# motor_board.net
KiCad netlist of a schematic drawn in EAGLE
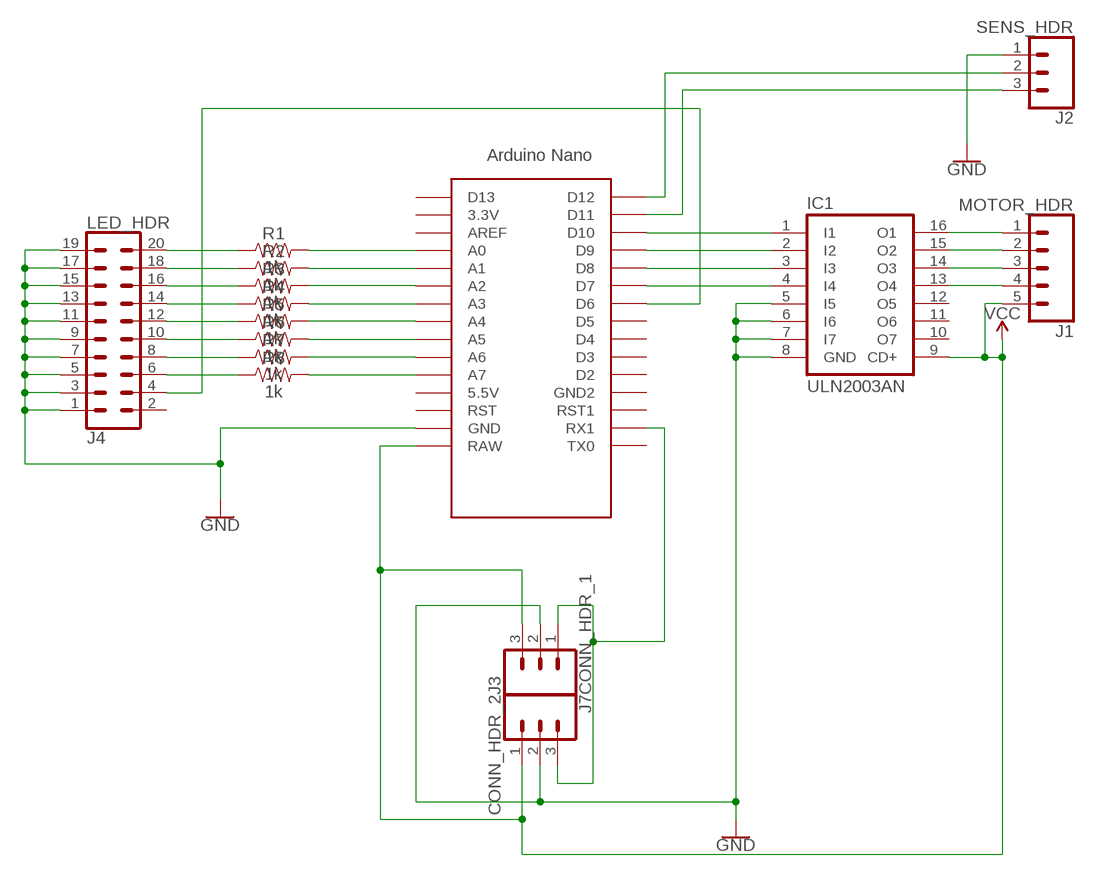
[diagram p0: schematic, sheet 1]

(export (version "E")
  (design (tool "Eeschema 10.0.6"))
  (components
    (comp (ref "IC1")
      (value "ULN2003AN")
      (footprint "eagle-import:DIL16")
      (libsource (lib "eagle-import") (part "ULN2003AN"))
    )
    (comp (ref "J1")
      (value "MOTOR_HDR")
      (footprint "eagle-import:1X05")
      (libsource (lib "eagle-import") (part "CONN_05"))
    )
    (comp (ref "J2")
      (value "SENS_HDR")
      (footprint "eagle-import:1X03")
      (libsource (lib "eagle-import") (part "CONN_03"))
    )
    (comp (ref "J3")
      (value "CONN_HDR_1")
      (footprint "eagle-import:1X03")
      (libsource (lib "eagle-import") (part "CONN_03"))
    )
    (comp (ref "J4")
      (value "LED_HDR")
      (footprint "eagle-import:2X10")
      (libsource (lib "eagle-import") (part "CONN_10X2"))
    )
    (comp (ref "J7")
      (value "CONN_HDR_2")
      (footprint "eagle-import:1X03")
      (libsource (lib "eagle-import") (part "CONN_03"))
    )
    (comp (ref "R1")
      (value "1k")
      (footprint "eagle-import:AXIAL-0.3")
      (libsource (lib "eagle-import") (part "1KOHM-HORIZ-1/4W-1%"))
    )
    (comp (ref "R2")
      (value "1k")
      (footprint "eagle-import:AXIAL-0.3")
      (libsource (lib "eagle-import") (part "1KOHM-HORIZ-1/4W-1%"))
    )
    (comp (ref "R3")
      (value "1k")
      (footprint "eagle-import:AXIAL-0.3")
      (libsource (lib "eagle-import") (part "1KOHM-HORIZ-1/4W-1%"))
    )
    (comp (ref "R4")
      (value "1k")
      (footprint "eagle-import:AXIAL-0.3")
      (libsource (lib "eagle-import") (part "1KOHM-HORIZ-1/4W-1%"))
    )
    (comp (ref "R5")
      (value "1k")
      (footprint "eagle-import:AXIAL-0.3")
      (libsource (lib "eagle-import") (part "1KOHM-HORIZ-1/4W-1%"))
    )
    (comp (ref "R6")
      (value "1k")
      (footprint "eagle-import:AXIAL-0.3")
      (libsource (lib "eagle-import") (part "1KOHM-HORIZ-1/4W-1%"))
    )
    (comp (ref "R7")
      (value "1k")
      (footprint "eagle-import:AXIAL-0.3")
      (libsource (lib "eagle-import") (part "1KOHM-HORIZ-1/4W-1%"))
    )
    (comp (ref "R8")
      (value "1k")
      (footprint "eagle-import:AXIAL-0.3")
      (libsource (lib "eagle-import") (part "1KOHM-HORIZ-1/4W-1%"))
    )
    (comp (ref "U$1")
      (value "NANO")
      (footprint "eagle-import:NANO")
      (libsource (lib "eagle-import") (part "NANO"))
    )
  )
  (nets
    (net (code "1") (name "GND") (class "Default")
      (node (ref "IC1") (pin "5") (pinfunction "I5_5") (pintype "input"))
      (node (ref "IC1") (pin "6") (pinfunction "I6_6") (pintype "input"))
      (node (ref "IC1") (pin "7") (pinfunction "I7_7") (pintype "input"))
      (node (ref "IC1") (pin "8") (pinfunction "GND_8") (pintype "power_in"))
      (node (ref "J2") (pin "1") (pinfunction "1_1") (pintype "passive"))
      (node (ref "J3") (pin "2") (pinfunction "2_2") (pintype "passive"))
      (node (ref "J4") (pin "1") (pinfunction "1_1") (pintype "passive"))
      (node (ref "J4") (pin "11") (pinfunction "11_11") (pintype "passive"))
      (node (ref "J4") (pin "13") (pinfunction "13_13") (pintype "passive"))
      (node (ref "J4") (pin "15") (pinfunction "15_15") (pintype "passive"))
      (node (ref "J4") (pin "17") (pinfunction "17_17") (pintype "passive"))
      (node (ref "J4") (pin "19") (pinfunction "19_19") (pintype "passive"))
      (node (ref "J4") (pin "3") (pinfunction "3_3") (pintype "passive"))
      (node (ref "J4") (pin "5") (pinfunction "5_5") (pintype "passive"))
      (node (ref "J4") (pin "7") (pinfunction "7_7") (pintype "passive"))
      (node (ref "J4") (pin "9") (pinfunction "9_9") (pintype "passive"))
      (node (ref "J7") (pin "2") (pinfunction "2_2") (pintype "passive"))
      (node (ref "U$1") (pin "GND") (pinfunction "GND_GND") (pintype "bidirectional"))
    )
    (net (code "2") (name "Net-(IC1-I1)") (class "Default")
      (node (ref "IC1") (pin "1") (pinfunction "I1_1") (pintype "input"))
      (node (ref "U$1") (pin "D10") (pinfunction "D10_D10") (pintype "bidirectional"))
    )
    (net (code "3") (name "Net-(IC1-I2)") (class "Default")
      (node (ref "IC1") (pin "2") (pinfunction "I2_2") (pintype "input"))
      (node (ref "U$1") (pin "D9") (pinfunction "D9_D9") (pintype "bidirectional"))
    )
    (net (code "4") (name "Net-(IC1-I3)") (class "Default")
      (node (ref "IC1") (pin "3") (pinfunction "I3_3") (pintype "input"))
      (node (ref "U$1") (pin "D8") (pinfunction "D8_D8") (pintype "bidirectional"))
    )
    (net (code "5") (name "Net-(IC1-I4)") (class "Default")
      (node (ref "IC1") (pin "4") (pinfunction "I4_4") (pintype "input"))
      (node (ref "U$1") (pin "D7") (pinfunction "D7_D7") (pintype "bidirectional"))
    )
    (net (code "6") (name "Net-(IC1-O1)") (class "Default")
      (node (ref "IC1") (pin "16") (pinfunction "O1_16") (pintype "open_collector"))
      (node (ref "J1") (pin "1") (pinfunction "1_1") (pintype "passive"))
    )
    (net (code "7") (name "Net-(IC1-O2)") (class "Default")
      (node (ref "IC1") (pin "15") (pinfunction "O2_15") (pintype "open_collector"))
      (node (ref "J1") (pin "2") (pinfunction "2_2") (pintype "passive"))
    )
    (net (code "8") (name "Net-(IC1-O3)") (class "Default")
      (node (ref "IC1") (pin "14") (pinfunction "O3_14") (pintype "open_collector"))
      (node (ref "J1") (pin "3") (pinfunction "3_3") (pintype "passive"))
    )
    (net (code "9") (name "Net-(IC1-O4)") (class "Default")
      (node (ref "IC1") (pin "13") (pinfunction "O4_13") (pintype "open_collector"))
      (node (ref "J1") (pin "4") (pinfunction "4_4") (pintype "passive"))
    )
    (net (code "10") (name "Net-(J2-Pad2)") (class "Default")
      (node (ref "J2") (pin "2") (pinfunction "2_2") (pintype "passive"))
      (node (ref "U$1") (pin "D12") (pinfunction "D12_D12") (pintype "bidirectional"))
    )
    (net (code "11") (name "Net-(J2-Pad3)") (class "Default")
      (node (ref "J2") (pin "3") (pinfunction "3_3") (pintype "passive"))
      (node (ref "U$1") (pin "D11") (pinfunction "D11_D11") (pintype "bidirectional"))
    )
    (net (code "12") (name "Net-(J3-Pad1)") (class "Default")
      (node (ref "J3") (pin "1") (pinfunction "1_1") (pintype "passive"))
      (node (ref "J7") (pin "3") (pinfunction "3_3") (pintype "passive"))
      (node (ref "U$1") (pin "RX1") (pinfunction "RX1_RX1") (pintype "bidirectional"))
    )
    (net (code "13") (name "Net-(J4-Pad4)") (class "Default")
      (node (ref "J4") (pin "4") (pinfunction "4_4") (pintype "passive"))
      (node (ref "U$1") (pin "D6") (pinfunction "D6_D6") (pintype "bidirectional"))
    )
    (net (code "14") (name "Net-(R1-1)") (class "Default")
      (node (ref "J4") (pin "20") (pinfunction "20_20") (pintype "passive"))
      (node (ref "R1") (pin "P$1") (pinfunction "1_P$1") (pintype "passive"))
    )
    (net (code "15") (name "Net-(R1-2)") (class "Default")
      (node (ref "R1") (pin "P$2") (pinfunction "2_P$2") (pintype "passive"))
      (node (ref "U$1") (pin "A0") (pinfunction "A0_A0") (pintype "bidirectional"))
    )
    (net (code "16") (name "Net-(R2-1)") (class "Default")
      (node (ref "J4") (pin "18") (pinfunction "18_18") (pintype "passive"))
      (node (ref "R2") (pin "P$1") (pinfunction "1_P$1") (pintype "passive"))
    )
    (net (code "17") (name "Net-(R2-2)") (class "Default")
      (node (ref "R2") (pin "P$2") (pinfunction "2_P$2") (pintype "passive"))
      (node (ref "U$1") (pin "A1") (pinfunction "A1_A1") (pintype "bidirectional"))
    )
    (net (code "18") (name "Net-(R3-1)") (class "Default")
      (node (ref "J4") (pin "16") (pinfunction "16_16") (pintype "passive"))
      (node (ref "R3") (pin "P$1") (pinfunction "1_P$1") (pintype "passive"))
    )
    (net (code "19") (name "Net-(R3-2)") (class "Default")
      (node (ref "R3") (pin "P$2") (pinfunction "2_P$2") (pintype "passive"))
      (node (ref "U$1") (pin "A2") (pinfunction "A2_A2") (pintype "bidirectional"))
    )
    (net (code "20") (name "Net-(R4-1)") (class "Default")
      (node (ref "J4") (pin "14") (pinfunction "14_14") (pintype "passive"))
      (node (ref "R4") (pin "P$1") (pinfunction "1_P$1") (pintype "passive"))
    )
    (net (code "21") (name "Net-(R4-2)") (class "Default")
      (node (ref "R4") (pin "P$2") (pinfunction "2_P$2") (pintype "passive"))
      (node (ref "U$1") (pin "A3") (pinfunction "A3_A3") (pintype "bidirectional"))
    )
    (net (code "22") (name "Net-(R5-1)") (class "Default")
      (node (ref "J4") (pin "12") (pinfunction "12_12") (pintype "passive"))
      (node (ref "R5") (pin "P$1") (pinfunction "1_P$1") (pintype "passive"))
    )
    (net (code "23") (name "Net-(R5-2)") (class "Default")
      (node (ref "R5") (pin "P$2") (pinfunction "2_P$2") (pintype "passive"))
      (node (ref "U$1") (pin "A4") (pinfunction "A4_A4") (pintype "bidirectional"))
    )
    (net (code "24") (name "Net-(R6-1)") (class "Default")
      (node (ref "J4") (pin "10") (pinfunction "10_10") (pintype "passive"))
      (node (ref "R6") (pin "P$1") (pinfunction "1_P$1") (pintype "passive"))
    )
    (net (code "25") (name "Net-(R6-2)") (class "Default")
      (node (ref "R6") (pin "P$2") (pinfunction "2_P$2") (pintype "passive"))
      (node (ref "U$1") (pin "A5") (pinfunction "A5_A5") (pintype "bidirectional"))
    )
    (net (code "26") (name "Net-(R7-1)") (class "Default")
      (node (ref "J4") (pin "8") (pinfunction "8_8") (pintype "passive"))
      (node (ref "R7") (pin "P$1") (pinfunction "1_P$1") (pintype "passive"))
    )
    (net (code "27") (name "Net-(R7-2)") (class "Default")
      (node (ref "R7") (pin "P$2") (pinfunction "2_P$2") (pintype "passive"))
      (node (ref "U$1") (pin "A6") (pinfunction "A6_A6") (pintype "bidirectional"))
    )
    (net (code "28") (name "Net-(R8-1)") (class "Default")
      (node (ref "J4") (pin "6") (pinfunction "6_6") (pintype "passive"))
      (node (ref "R8") (pin "P$1") (pinfunction "1_P$1") (pintype "passive"))
    )
    (net (code "29") (name "Net-(R8-2)") (class "Default")
      (node (ref "R8") (pin "P$2") (pinfunction "2_P$2") (pintype "passive"))
      (node (ref "U$1") (pin "A7") (pinfunction "A7_A7") (pintype "bidirectional"))
    )
    (net (code "30") (name "VCC") (class "Default")
      (node (ref "IC1") (pin "9") (pinfunction "CD+_9") (pintype "passive"))
      (node (ref "J1") (pin "5") (pinfunction "5_5") (pintype "passive"))
      (node (ref "J3") (pin "3") (pinfunction "3_3") (pintype "passive"))
      (node (ref "J7") (pin "1") (pinfunction "1_1") (pintype "passive"))
      (node (ref "U$1") (pin "RAW") (pinfunction "RAW_RAW") (pintype "bidirectional"))
    )
    (net (code "31") (name "unconnected-(IC1-O5-Pad12)") (class "Default")
      (node (ref "IC1") (pin "12") (pinfunction "O5_12") (pintype "open_collector"))
    )
    (net (code "32") (name "unconnected-(IC1-O6-Pad11)") (class "Default")
      (node (ref "IC1") (pin "11") (pinfunction "O6_11") (pintype "open_collector"))
    )
    (net (code "33") (name "unconnected-(IC1-O7-Pad10)") (class "Default")
      (node (ref "IC1") (pin "10") (pinfunction "O7_10") (pintype "open_collector"))
    )
    (net (code "34") (name "unconnected-(J4-Pad2)") (class "Default")
      (node (ref "J4") (pin "2") (pinfunction "2_2") (pintype "passive"))
    )
    (net (code "35") (name "unconnected-(U$1-5.5V-Pad5V)") (class "Default")
      (node (ref "U$1") (pin "5V") (pinfunction "5.5V_5V") (pintype "bidirectional"))
    )
    (net (code "36") (name "unconnected-(U$1-GND2-PadGND1)") (class "Default")
      (node (ref "U$1") (pin "GND1") (pinfunction "GND2_GND1") (pintype "bidirectional"))
    )
    (net (code "37") (name "unconnected-(U$1-Pad3.3V)") (class "Default")
      (node (ref "U$1") (pin "3.3V") (pinfunction "3.3V_3.3V") (pintype "bidirectional"))
    )
    (net (code "38") (name "unconnected-(U$1-PadAREF)") (class "Default")
      (node (ref "U$1") (pin "AREF") (pinfunction "AREF_AREF") (pintype "bidirectional"))
    )
    (net (code "39") (name "unconnected-(U$1-PadD2)") (class "Default")
      (node (ref "U$1") (pin "D2") (pinfunction "D2_D2") (pintype "bidirectional"))
    )
    (net (code "40") (name "unconnected-(U$1-PadD3)") (class "Default")
      (node (ref "U$1") (pin "D3") (pinfunction "D3_D3") (pintype "bidirectional"))
    )
    (net (code "41") (name "unconnected-(U$1-PadD4)") (class "Default")
      (node (ref "U$1") (pin "D4") (pinfunction "D4_D4") (pintype "bidirectional"))
    )
    (net (code "42") (name "unconnected-(U$1-PadD5)") (class "Default")
      (node (ref "U$1") (pin "D5") (pinfunction "D5_D5") (pintype "bidirectional"))
    )
    (net (code "43") (name "unconnected-(U$1-PadD13)") (class "Default")
      (node (ref "U$1") (pin "D13") (pinfunction "D13_D13") (pintype "bidirectional"))
    )
    (net (code "44") (name "unconnected-(U$1-PadICSP1)") (class "Default")
      (node (ref "U$1") (pin "ICSP1") (pinfunction "ICSP1_ICSP1") (pintype "bidirectional"))
    )
    (net (code "45") (name "unconnected-(U$1-PadICSP2)") (class "Default")
      (node (ref "U$1") (pin "ICSP2") (pinfunction "ICSP2_ICSP2") (pintype "bidirectional"))
    )
    (net (code "46") (name "unconnected-(U$1-PadICSP3)") (class "Default")
      (node (ref "U$1") (pin "ICSP3") (pinfunction "ICSP3_ICSP3") (pintype "bidirectional"))
    )
    (net (code "47") (name "unconnected-(U$1-PadICSP4)") (class "Default")
      (node (ref "U$1") (pin "ICSP4") (pinfunction "ICSP4_ICSP4") (pintype "bidirectional"))
    )
    (net (code "48") (name "unconnected-(U$1-PadICSP5)") (class "Default")
      (node (ref "U$1") (pin "ICSP5") (pinfunction "ICSP5_ICSP5") (pintype "bidirectional"))
    )
    (net (code "49") (name "unconnected-(U$1-PadICSP6)") (class "Default")
      (node (ref "U$1") (pin "ICSP6") (pinfunction "ICSP6_ICSP6") (pintype "bidirectional"))
    )
    (net (code "50") (name "unconnected-(U$1-PadRST)") (class "Default")
      (node (ref "U$1") (pin "RST") (pinfunction "RST_RST") (pintype "bidirectional"))
    )
    (net (code "51") (name "unconnected-(U$1-PadRST1)") (class "Default")
      (node (ref "U$1") (pin "RST1") (pinfunction "RST1_RST1") (pintype "bidirectional"))
    )
    (net (code "52") (name "unconnected-(U$1-PadTX0)") (class "Default")
      (node (ref "U$1") (pin "TX0") (pinfunction "TX0_TX0") (pintype "bidirectional"))
    )
  )
)
